# template_esp32.net
KiCad netlist of a schematic drawn in EAGLE
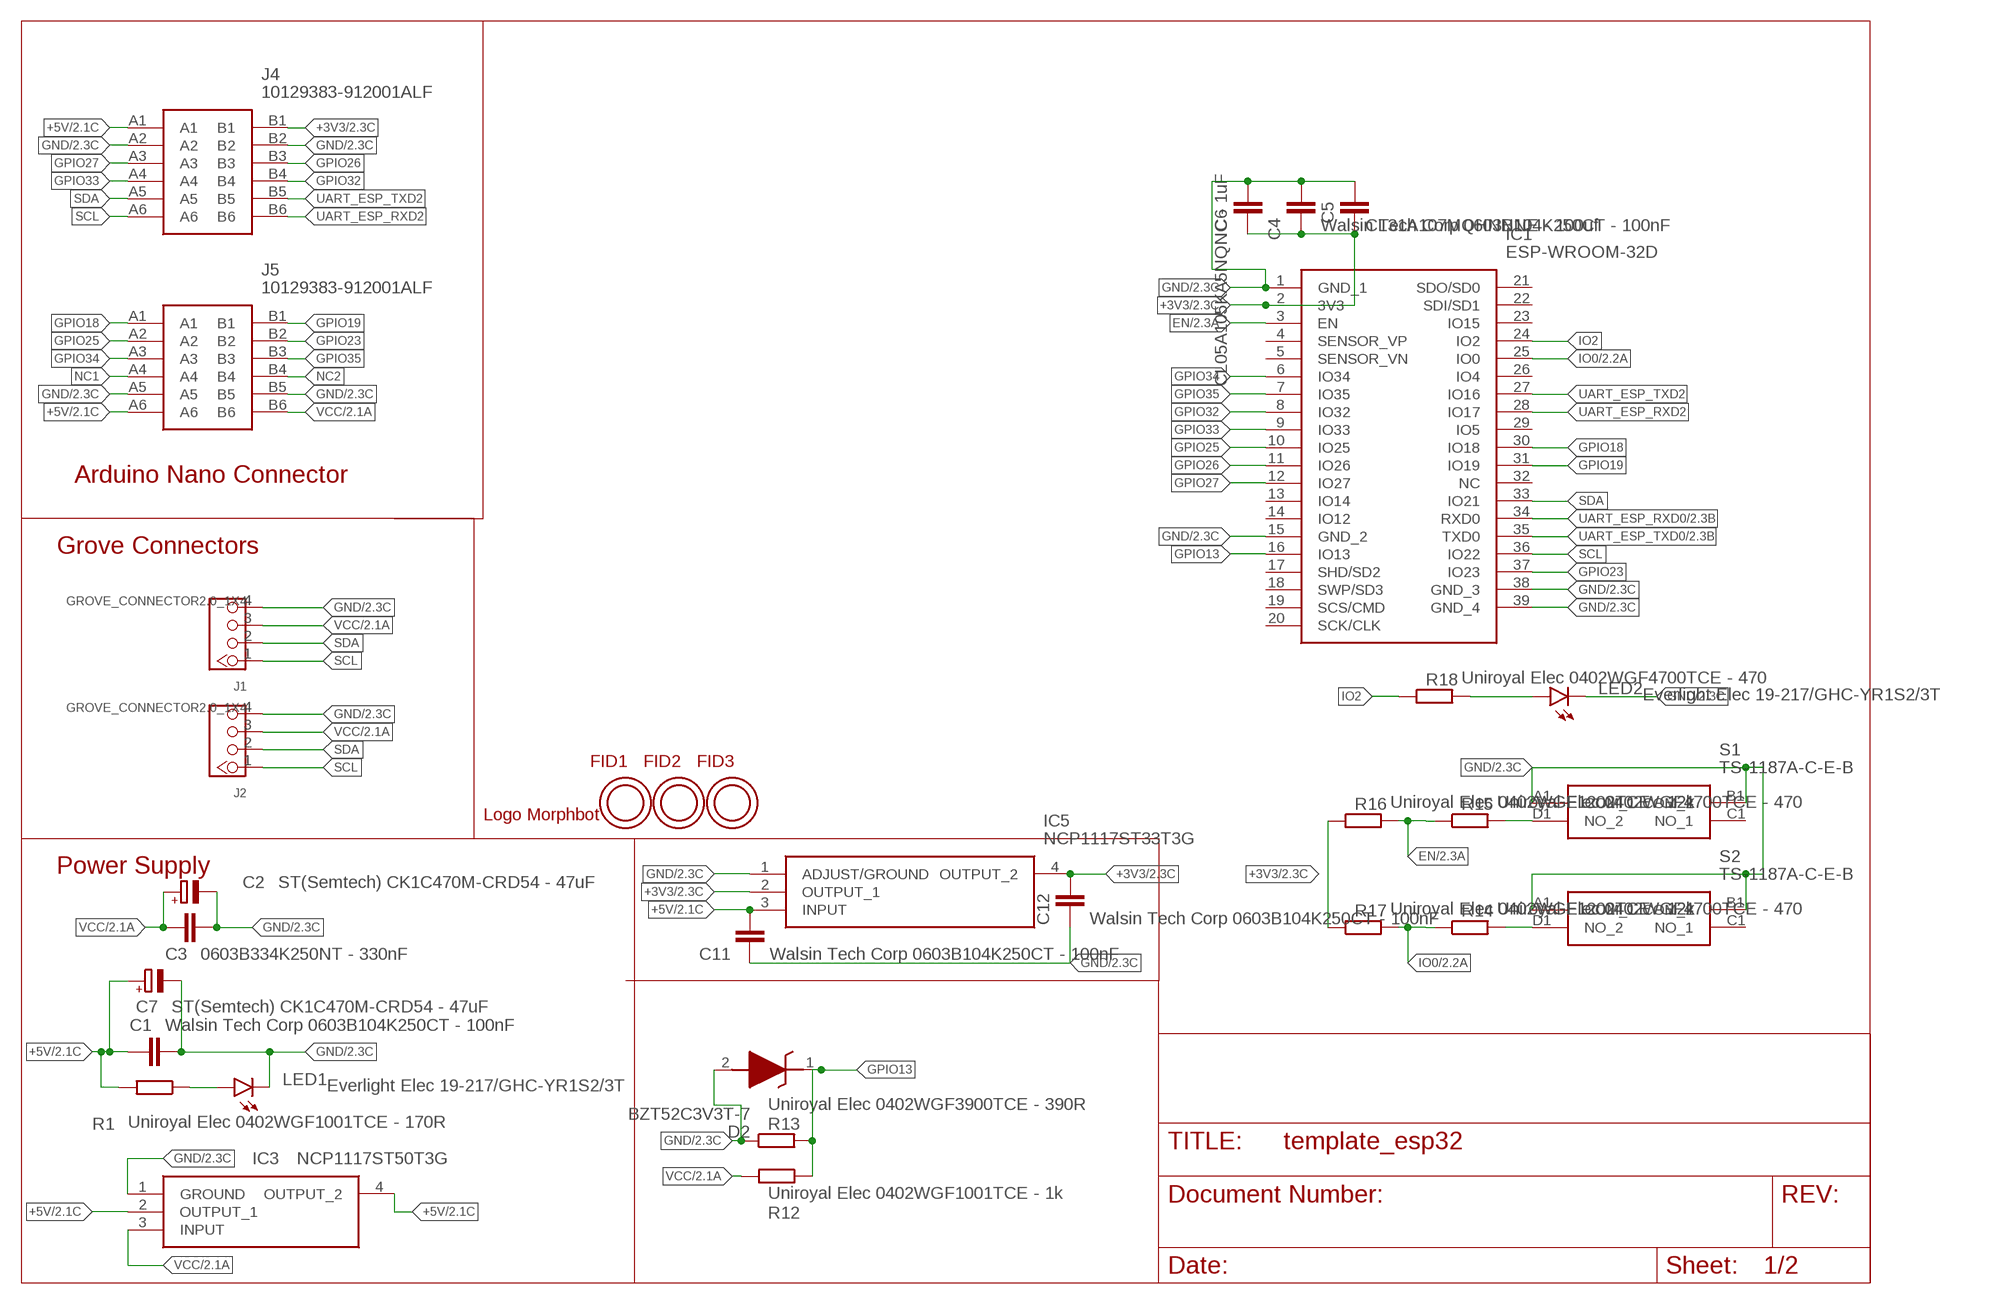
[diagram p0: schematic, sheet 1]
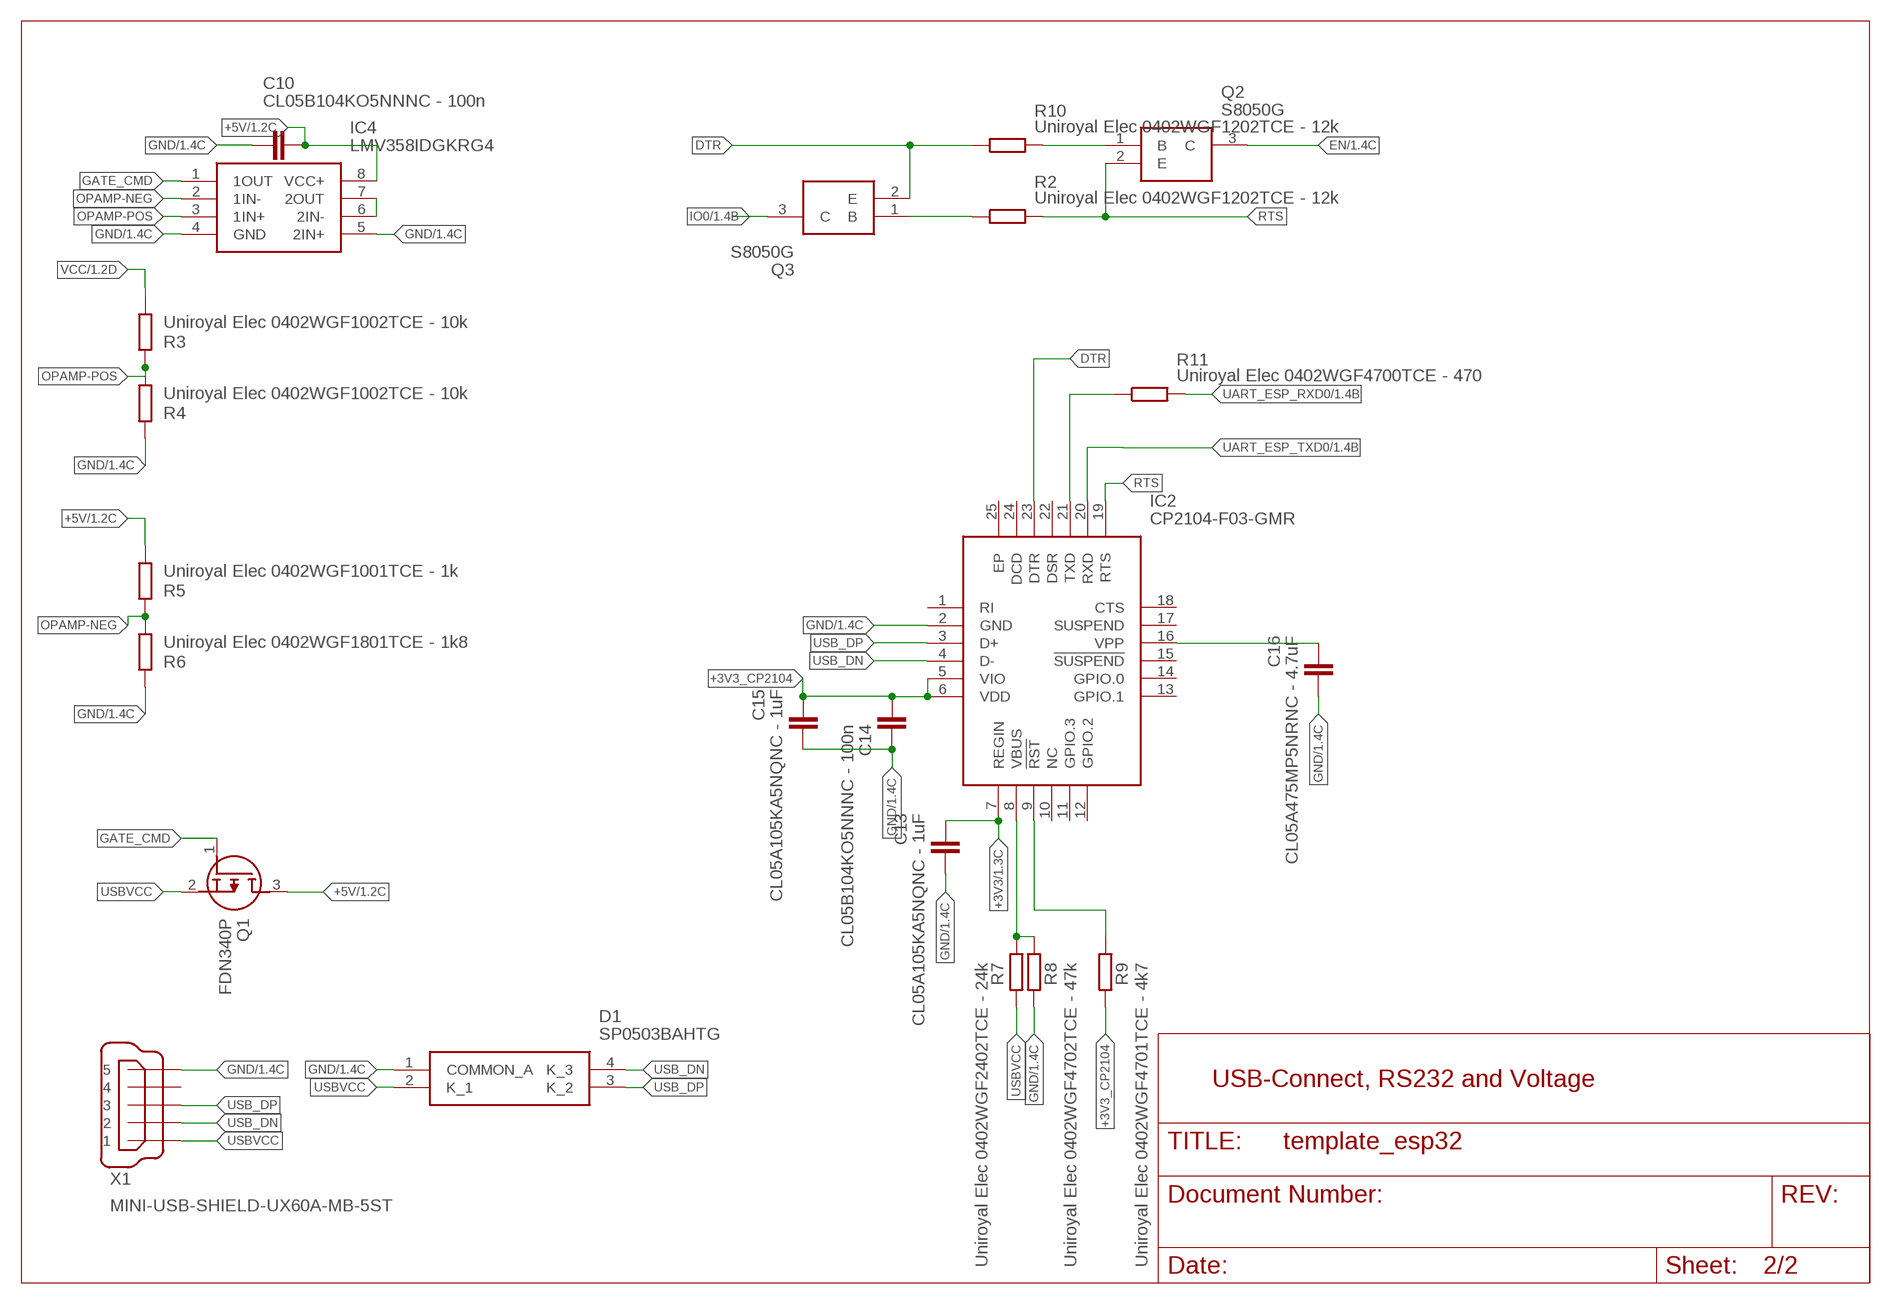
[diagram p1: schematic, sheet 2]

(export (version "E")
  (design (tool "Eeschema 10.0.6"))
  (components
    (comp (ref "C1")
      (value "Walsin Tech Corp 0603B104K250CT - 100nF")
      (footprint "eagle-import:C0603")
      (libsource (lib "eagle-import") (part "C-EUC0603"))
    )
    (comp (ref "C2")
      (value "ST(Semtech) CK1C470M-CRD54 - 47uF")
      (footprint "eagle-import:PANASONIC_C")
      (libsource (lib "eagle-import") (part "CPOL-EUC"))
    )
    (comp (ref "C3")
      (value "0603B334K250NT - 330nF")
      (footprint "eagle-import:C0603")
      (libsource (lib "eagle-import") (part "C-EUC0603"))
    )
    (comp (ref "C4")
      (value "Walsin Tech Corp 0603B104K250CT - 100nF")
      (footprint "eagle-import:C0603")
      (libsource (lib "eagle-import") (part "C-EUC0603"))
    )
    (comp (ref "C5")
      (value "CL31A107MQHNNNE - 100uf")
      (footprint "eagle-import:C1206")
      (libsource (lib "eagle-import") (part "C-EUC1206"))
    )
    (comp (ref "C6")
      (value "CL05A105KA5NQNC - 1uF")
      (footprint "eagle-import:C0402")
      (libsource (lib "eagle-import") (part "C-EUC0402"))
    )
    (comp (ref "C7")
      (value "ST(Semtech) CK1C470M-CRD54 - 47uF")
      (footprint "eagle-import:PANASONIC_C")
      (libsource (lib "eagle-import") (part "CPOL-EUC"))
    )
    (comp (ref "C11")
      (value "Walsin Tech Corp 0603B104K250CT - 100nF")
      (footprint "eagle-import:C0603")
      (libsource (lib "eagle-import") (part "C-EUC0603"))
    )
    (comp (ref "C12")
      (value "Walsin Tech Corp 0603B104K250CT - 100nF")
      (footprint "eagle-import:C0603")
      (libsource (lib "eagle-import") (part "C-EUC0603"))
    )
    (comp (ref "D2")
      (value "BZT52C3V3T-7")
      (footprint "eagle-import:SODFL1608X65N")
      (fields (field (name "MOUSER_PART_NUMBER") "621-BZT52C3V3T-7"))
      (libsource (lib "eagle-import") (part "BZT52C3V3T-7"))
    )
    (comp (ref "FID1")
      (value "OPEN-PNP-FIDUCIAL")
      (footprint "eagle-import:OPEN-PNP-FIDUCIAL")
      (libsource (lib "eagle-import") (part "OPEN-PNP-FIDUCIAL"))
    )
    (comp (ref "FID2")
      (value "OPEN-PNP-FIDUCIAL")
      (footprint "eagle-import:OPEN-PNP-FIDUCIAL")
      (libsource (lib "eagle-import") (part "OPEN-PNP-FIDUCIAL"))
    )
    (comp (ref "FID3")
      (value "OPEN-PNP-FIDUCIAL")
      (footprint "eagle-import:OPEN-PNP-FIDUCIAL")
      (libsource (lib "eagle-import") (part "OPEN-PNP-FIDUCIAL"))
    )
    (comp (ref "IC1")
      (value "ESP-WROOM-32D")
      (footprint "eagle-import:ESPWROOM32D")
      (fields (field (name "MOUSER_PART_NUMBER") "356-ESP-WROOM-32D"))
      (libsource (lib "eagle-import") (part "ESP-WROOM-32D"))
    )
    (comp (ref "IC3")
      (value "NCP1117ST50T3G")
      (footprint "eagle-import:SOT230P700X180-4N")
      (fields (field (name "MOUSER_PART_NUMBER") "863-NCP1117ST50T3G"))
      (libsource (lib "eagle-import") (part "NCP1117ST50T3G"))
    )
    (comp (ref "IC5")
      (value "NCP1117ST33T3G")
      (footprint "eagle-import:SOT230P700X180-4N")
      (fields (field (name "MOUSER_PART_NUMBER") "863-NCP1117ST33T3G"))
      (libsource (lib "eagle-import") (part "NCP1117ST33T3G"))
    )
    (comp (ref "J1")
      (value "GROVE_CONNECTOR2.0_1X4")
      (footprint "eagle-import:2.0_1X4_STRAIGHT")
      (libsource (lib "eagle-import") (part "GROVE_CONNECTOR2.0_1X4"))
    )
    (comp (ref "J2")
      (value "GROVE_CONNECTOR2.0_1X4")
      (footprint "eagle-import:2.0_1X4_STRAIGHT")
      (libsource (lib "eagle-import") (part "GROVE_CONNECTOR2.0_1X4"))
    )
    (comp (ref "J4")
      (value "10129383-912001ALF")
      (footprint "eagle-import:10129383912001ALF")
      (fields (field (name "MOUSER_PART_NUMBER") "649-1012938391201ALF"))
      (libsource (lib "eagle-import") (part "10129383-912001ALF"))
    )
    (comp (ref "J5")
      (value "10129383-912001ALF")
      (footprint "eagle-import:10129383912001ALF")
      (fields (field (name "MOUSER_PART_NUMBER") "649-1012938391201ALF"))
      (libsource (lib "eagle-import") (part "10129383-912001ALF"))
    )
    (comp (ref "LED1")
      (value "Everlight Elec 19-217/GHC-YR1S2/3T")
      (footprint "eagle-import:CHIPLED_0603")
      (libsource (lib "eagle-import") (part "LEDCHIPLED_0603"))
    )
    (comp (ref "LED2")
      (value "Everlight Elec 19-217/GHC-YR1S2/3T")
      (footprint "eagle-import:CHIPLED_0603")
      (libsource (lib "eagle-import") (part "LEDCHIPLED_0603"))
    )
    (comp (ref "R1")
      (value "Uniroyal Elec 0402WGF1001TCE - 170R")
      (footprint "eagle-import:R0402")
      (libsource (lib "eagle-import") (part "R-EU_R0402"))
    )
    (comp (ref "R12")
      (value "Uniroyal Elec 0402WGF1001TCE - 1k")
      (footprint "eagle-import:R0402")
      (libsource (lib "eagle-import") (part "R-EU_R0402"))
    )
    (comp (ref "R13")
      (value "Uniroyal Elec 0402WGF3900TCE - 390R")
      (footprint "eagle-import:R0402")
      (libsource (lib "eagle-import") (part "R-EU_R0402"))
    )
    (comp (ref "R14")
      (value "Uniroyal Elec 0402WGF4700TCE - 470")
      (footprint "eagle-import:R0402")
      (libsource (lib "eagle-import") (part "R-EU_R0402"))
    )
    (comp (ref "R15")
      (value "Uniroyal Elec 0402WGF4700TCE - 470")
      (footprint "eagle-import:R0402")
      (libsource (lib "eagle-import") (part "R-EU_R0402"))
    )
    (comp (ref "R16")
      (value "Uniroyal Elec 0402WGF1202TCE - 12k")
      (footprint "eagle-import:R0402")
      (libsource (lib "eagle-import") (part "R-EU_R0402"))
    )
    (comp (ref "R17")
      (value "Uniroyal Elec 0402WGF1202TCE - 12k")
      (footprint "eagle-import:R0402")
      (libsource (lib "eagle-import") (part "R-EU_R0402"))
    )
    (comp (ref "R18")
      (value "Uniroyal Elec 0402WGF4700TCE - 470")
      (footprint "eagle-import:R0402")
      (libsource (lib "eagle-import") (part "R-EU_R0402"))
    )
    (comp (ref "S1")
      (value "TS-1187A-C-E-B")
      (footprint "eagle-import:TS1187ACEB")
      (libsource (lib "eagle-import") (part "TS-1187A-C-E-B"))
    )
    (comp (ref "S2")
      (value "TS-1187A-C-E-B")
      (footprint "eagle-import:TS1187ACEB")
      (libsource (lib "eagle-import") (part "TS-1187A-C-E-B"))
    )
    (comp (ref "U$1")
      (value "LOGO_MORPHBOT3MM")
      (footprint "eagle-import:LOGO_MOPRHBOT_3MM")
      (libsource (lib "eagle-import") (part "LOGO_MORPHBOT3MM"))
    )
    (comp (ref "C10")
      (value "CL05B104KO5NNNC - 100n")
      (footprint "eagle-import:C0402")
      (libsource (lib "eagle-import") (part "C-EUC0402"))
    )
    (comp (ref "C13")
      (value "CL05A105KA5NQNC - 1uF")
      (footprint "eagle-import:C0402")
      (libsource (lib "eagle-import") (part "C-EUC0402"))
    )
    (comp (ref "C14")
      (value "CL05B104KO5NNNC - 100n")
      (footprint "eagle-import:C0402")
      (libsource (lib "eagle-import") (part "C-EUC0402"))
    )
    (comp (ref "C15")
      (value "CL05A105KA5NQNC - 1uF")
      (footprint "eagle-import:C0402")
      (libsource (lib "eagle-import") (part "C-EUC0402"))
    )
    (comp (ref "C16")
      (value "CL05A475MP5NRNC - 4.7uF")
      (footprint "eagle-import:C0402")
      (libsource (lib "eagle-import") (part "C-EUC0402"))
    )
    (comp (ref "D1")
      (value "SP0503BAHTG")
      (footprint "eagle-import:SP0503BAHTG")
      (fields (field (name "MOUSER_PART_NUMBER") "576-SP0503BAHTG"))
      (libsource (lib "eagle-import") (part "SP0503BAHTG"))
    )
    (comp (ref "IC2")
      (value "CP2104-F03-GMR")
      (footprint "eagle-import:QFN50P400X400X80-25N")
      (fields (field (name "MOUSER_PART_NUMBER") "634-CP2104-F03-GMR"))
      (libsource (lib "eagle-import") (part "CP2104-F03-GMR"))
    )
    (comp (ref "IC4")
      (value "LMV358IDGKRG4")
      (footprint "eagle-import:SOP65P490X110-8N")
      (fields (field (name "MOUSER_PART_NUMBER") "595-LMV358IDGKRG4"))
      (libsource (lib "eagle-import") (part "LMV358IDGKRG4"))
    )
    (comp (ref "Q1")
      (value "FDN340P")
      (footprint "eagle-import:SOT95P237X112-3N")
      (fields (field (name "MOUSER_PART_NUMBER") "512-FDN340P"))
      (libsource (lib "eagle-import") (part "FDN340P"))
    )
    (comp (ref "Q2")
      (value "S8050G")
      (footprint "eagle-import:SOT95P240X110-3N")
      (libsource (lib "eagle-import") (part "S8050G"))
    )
    (comp (ref "Q3")
      (value "S8050G")
      (footprint "eagle-import:SOT95P240X110-3N")
      (libsource (lib "eagle-import") (part "S8050G"))
    )
    (comp (ref "R2")
      (value "Uniroyal Elec 0402WGF1202TCE - 12k")
      (footprint "eagle-import:R0402")
      (libsource (lib "eagle-import") (part "R-EU_R0402"))
    )
    (comp (ref "R3")
      (value "Uniroyal Elec 0402WGF1002TCE - 10k")
      (footprint "eagle-import:R0402")
      (libsource (lib "eagle-import") (part "R-EU_R0402"))
    )
    (comp (ref "R4")
      (value "Uniroyal Elec 0402WGF1002TCE - 10k")
      (footprint "eagle-import:R0402")
      (libsource (lib "eagle-import") (part "R-EU_R0402"))
    )
    (comp (ref "R5")
      (value "Uniroyal Elec 0402WGF1001TCE - 1k")
      (footprint "eagle-import:R0402")
      (libsource (lib "eagle-import") (part "R-EU_R0402"))
    )
    (comp (ref "R6")
      (value "Uniroyal Elec 0402WGF1801TCE - 1k8")
      (footprint "eagle-import:R0402")
      (libsource (lib "eagle-import") (part "R-EU_R0402"))
    )
    (comp (ref "R7")
      (value "Uniroyal Elec 0402WGF2402TCE - 24k")
      (footprint "eagle-import:R0402")
      (libsource (lib "eagle-import") (part "R-EU_R0402"))
    )
    (comp (ref "R8")
      (value "Uniroyal Elec 0402WGF4702TCE - 47k")
      (footprint "eagle-import:R0402")
      (libsource (lib "eagle-import") (part "R-EU_R0402"))
    )
    (comp (ref "R9")
      (value "Uniroyal Elec 0402WGF4701TCE - 4k7")
      (footprint "eagle-import:R0402")
      (libsource (lib "eagle-import") (part "R-EU_R0402"))
    )
    (comp (ref "R10")
      (value "Uniroyal Elec 0402WGF1202TCE - 12k")
      (footprint "eagle-import:R0402")
      (libsource (lib "eagle-import") (part "R-EU_R0402"))
    )
    (comp (ref "R11")
      (value "Uniroyal Elec 0402WGF4700TCE - 470")
      (footprint "eagle-import:R0402")
      (libsource (lib "eagle-import") (part "R-EU_R0402"))
    )
    (comp (ref "X1")
      (value "MINI-USB-SHIELD-UX60A-MB-5ST")
      (footprint "eagle-import:UX60A-MB-5ST")
      (libsource (lib "eagle-import") (part "MINI-USB-SHIELD-UX60A-MB-5ST"))
    )
  )
  (nets
    (net (code "1") (name "+3V3") (class "Default")
      (node (ref "C12") (pin "2") (pinfunction "2_2") (pintype "passive"))
      (node (ref "C13") (pin "2") (pinfunction "2_2") (pintype "passive"))
      (node (ref "C4") (pin "1") (pinfunction "1_1") (pintype "passive"))
      (node (ref "C5") (pin "2") (pinfunction "2_2") (pintype "passive"))
      (node (ref "C6") (pin "1") (pinfunction "1_1") (pintype "passive"))
      (node (ref "IC1") (pin "2") (pinfunction "3V3_2") (pintype "bidirectional"))
      (node (ref "IC2") (pin "7") (pinfunction "REGIN_7") (pintype "bidirectional"))
      (node (ref "IC5") (pin "2") (pinfunction "OUTPUT_1_2") (pintype "bidirectional"))
      (node (ref "IC5") (pin "4") (pinfunction "OUTPUT_2_4") (pintype "bidirectional"))
      (node (ref "J4") (pin "B1") (pinfunction "B1_B1") (pintype "bidirectional"))
      (node (ref "R16") (pin "1") (pinfunction "1_1") (pintype "passive"))
      (node (ref "R17") (pin "1") (pinfunction "1_1") (pintype "passive"))
    )
    (net (code "2") (name "+3V3_CP2104") (class "Default")
      (node (ref "C14") (pin "2") (pinfunction "2_2") (pintype "passive"))
      (node (ref "C15") (pin "2") (pinfunction "2_2") (pintype "passive"))
      (node (ref "IC2") (pin "5") (pinfunction "VIO_5") (pintype "bidirectional"))
      (node (ref "IC2") (pin "6") (pinfunction "VDD_6") (pintype "bidirectional"))
      (node (ref "R9") (pin "2") (pinfunction "2_2") (pintype "passive"))
    )
    (net (code "3") (name "+5V") (class "Default")
      (node (ref "C1") (pin "1") (pinfunction "1_1") (pintype "passive"))
      (node (ref "C10") (pin "2") (pinfunction "2_2") (pintype "passive"))
      (node (ref "C11") (pin "2") (pinfunction "2_2") (pintype "passive"))
      (node (ref "C7") (pin "+") (pinfunction "+_+") (pintype "passive"))
      (node (ref "IC3") (pin "2") (pinfunction "OUTPUT_1_2") (pintype "bidirectional"))
      (node (ref "IC3") (pin "4") (pinfunction "OUTPUT_2_4") (pintype "bidirectional"))
      (node (ref "IC4") (pin "8") (pinfunction "VCC+_8") (pintype "bidirectional"))
      (node (ref "IC5") (pin "3") (pinfunction "INPUT_3") (pintype "bidirectional"))
      (node (ref "J4") (pin "A1") (pinfunction "A1_A1") (pintype "bidirectional"))
      (node (ref "J5") (pin "A6") (pinfunction "A6_A6") (pintype "bidirectional"))
      (node (ref "Q1") (pin "3") (pinfunction "D_3") (pintype "bidirectional"))
      (node (ref "R1") (pin "2") (pinfunction "2_2") (pintype "passive"))
      (node (ref "R5") (pin "1") (pinfunction "1_1") (pintype "passive"))
    )
    (net (code "4") (name "DTR") (class "Default")
      (node (ref "IC2") (pin "23") (pinfunction "DTR_23") (pintype "bidirectional"))
      (node (ref "Q3") (pin "2") (pinfunction "E_2") (pintype "bidirectional"))
      (node (ref "R10") (pin "1") (pinfunction "1_1") (pintype "passive"))
    )
    (net (code "5") (name "EN") (class "Default")
      (node (ref "IC1") (pin "3") (pinfunction "EN_3") (pintype "bidirectional"))
      (node (ref "Q2") (pin "3") (pinfunction "C_3") (pintype "bidirectional"))
      (node (ref "R15") (pin "1") (pinfunction "1_1") (pintype "passive"))
      (node (ref "R16") (pin "2") (pinfunction "2_2") (pintype "passive"))
    )
    (net (code "6") (name "GATE_CMD") (class "Default")
      (node (ref "IC4") (pin "1") (pinfunction "1OUT_1") (pintype "bidirectional"))
      (node (ref "Q1") (pin "1") (pinfunction "G_1") (pintype "bidirectional"))
    )
    (net (code "7") (name "GND") (class "Default")
      (node (ref "C1") (pin "2") (pinfunction "2_2") (pintype "passive"))
      (node (ref "C10") (pin "1") (pinfunction "1_1") (pintype "passive"))
      (node (ref "C11") (pin "1") (pinfunction "1_1") (pintype "passive"))
      (node (ref "C12") (pin "1") (pinfunction "1_1") (pintype "passive"))
      (node (ref "C13") (pin "1") (pinfunction "1_1") (pintype "passive"))
      (node (ref "C14") (pin "1") (pinfunction "1_1") (pintype "passive"))
      (node (ref "C15") (pin "1") (pinfunction "1_1") (pintype "passive"))
      (node (ref "C16") (pin "1") (pinfunction "1_1") (pintype "passive"))
      (node (ref "C2") (pin "-") (pinfunction "-_-") (pintype "passive"))
      (node (ref "C3") (pin "1") (pinfunction "1_1") (pintype "passive"))
      (node (ref "C4") (pin "2") (pinfunction "2_2") (pintype "passive"))
      (node (ref "C5") (pin "1") (pinfunction "1_1") (pintype "passive"))
      (node (ref "C6") (pin "2") (pinfunction "2_2") (pintype "passive"))
      (node (ref "C7") (pin "-") (pinfunction "-_-") (pintype "passive"))
      (node (ref "D1") (pin "1") (pinfunction "COMMON_A_1") (pintype "bidirectional"))
      (node (ref "D2") (pin "2") (pinfunction "A_2") (pintype "bidirectional"))
      (node (ref "IC1") (pin "1") (pinfunction "GND_1_1") (pintype "bidirectional"))
      (node (ref "IC1") (pin "15") (pinfunction "GND_2_15") (pintype "bidirectional"))
      (node (ref "IC1") (pin "38") (pinfunction "GND_3_38") (pintype "bidirectional"))
      (node (ref "IC1") (pin "39") (pinfunction "GND_4_39") (pintype "bidirectional"))
      (node (ref "IC2") (pin "2") (pinfunction "GND_2") (pintype "bidirectional"))
      (node (ref "IC3") (pin "1") (pinfunction "GROUND_1") (pintype "bidirectional"))
      (node (ref "IC4") (pin "4") (pinfunction "GND_4") (pintype "bidirectional"))
      (node (ref "IC4") (pin "5") (pinfunction "2IN+_5") (pintype "bidirectional"))
      (node (ref "IC5") (pin "1") (pinfunction "ADJUST/GROUND_1") (pintype "bidirectional"))
      (node (ref "J1") (pin "4") (pinfunction "4_4") (pintype "bidirectional"))
      (node (ref "J2") (pin "4") (pinfunction "4_4") (pintype "bidirectional"))
      (node (ref "J4") (pin "A2") (pinfunction "A2_A2") (pintype "bidirectional"))
      (node (ref "J4") (pin "B2") (pinfunction "B2_B2") (pintype "bidirectional"))
      (node (ref "J5") (pin "A5") (pinfunction "A5_A5") (pintype "bidirectional"))
      (node (ref "J5") (pin "B5") (pinfunction "B5_B5") (pintype "bidirectional"))
      (node (ref "LED1") (pin "C") (pinfunction "C_C") (pintype "passive"))
      (node (ref "LED2") (pin "C") (pinfunction "C_C") (pintype "passive"))
      (node (ref "R13") (pin "1") (pinfunction "1_1") (pintype "passive"))
      (node (ref "R4") (pin "2") (pinfunction "2_2") (pintype "passive"))
      (node (ref "R6") (pin "2") (pinfunction "2_2") (pintype "passive"))
      (node (ref "R8") (pin "2") (pinfunction "2_2") (pintype "passive"))
      (node (ref "S1") (pin "A1") (pinfunction "COM_1_A1") (pintype "bidirectional"))
      (node (ref "S1") (pin "B1") (pinfunction "COM_2_B1") (pintype "bidirectional"))
      (node (ref "S2") (pin "A1") (pinfunction "COM_1_A1") (pintype "bidirectional"))
      (node (ref "S2") (pin "B1") (pinfunction "COM_2_B1") (pintype "bidirectional"))
      (node (ref "X1") (pin "5") (pinfunction "5_5") (pintype "input"))
    )
    (net (code "8") (name "GPIO13") (class "Default")
      (node (ref "D2") (pin "1") (pinfunction "K_1") (pintype "bidirectional"))
      (node (ref "IC1") (pin "16") (pinfunction "IO13_16") (pintype "bidirectional"))
      (node (ref "R12") (pin "1") (pinfunction "1_1") (pintype "passive"))
      (node (ref "R13") (pin "2") (pinfunction "2_2") (pintype "passive"))
    )
    (net (code "9") (name "GPIO18") (class "Default")
      (node (ref "IC1") (pin "30") (pinfunction "IO18_30") (pintype "bidirectional"))
      (node (ref "J5") (pin "A1") (pinfunction "A1_A1") (pintype "bidirectional"))
    )
    (net (code "10") (name "GPIO19") (class "Default")
      (node (ref "IC1") (pin "31") (pinfunction "IO19_31") (pintype "bidirectional"))
      (node (ref "J5") (pin "B1") (pinfunction "B1_B1") (pintype "bidirectional"))
    )
    (net (code "11") (name "GPIO23") (class "Default")
      (node (ref "IC1") (pin "37") (pinfunction "IO23_37") (pintype "bidirectional"))
      (node (ref "J5") (pin "B2") (pinfunction "B2_B2") (pintype "bidirectional"))
    )
    (net (code "12") (name "GPIO25") (class "Default")
      (node (ref "IC1") (pin "10") (pinfunction "IO25_10") (pintype "bidirectional"))
      (node (ref "J5") (pin "A2") (pinfunction "A2_A2") (pintype "bidirectional"))
    )
    (net (code "13") (name "GPIO26") (class "Default")
      (node (ref "IC1") (pin "11") (pinfunction "IO26_11") (pintype "bidirectional"))
      (node (ref "J4") (pin "B3") (pinfunction "B3_B3") (pintype "bidirectional"))
    )
    (net (code "14") (name "GPIO27") (class "Default")
      (node (ref "IC1") (pin "12") (pinfunction "IO27_12") (pintype "bidirectional"))
      (node (ref "J4") (pin "A3") (pinfunction "A3_A3") (pintype "bidirectional"))
    )
    (net (code "15") (name "GPIO32") (class "Default")
      (node (ref "IC1") (pin "8") (pinfunction "IO32_8") (pintype "bidirectional"))
      (node (ref "J4") (pin "B4") (pinfunction "B4_B4") (pintype "bidirectional"))
    )
    (net (code "16") (name "GPIO33") (class "Default")
      (node (ref "IC1") (pin "9") (pinfunction "IO33_9") (pintype "bidirectional"))
      (node (ref "J4") (pin "A4") (pinfunction "A4_A4") (pintype "bidirectional"))
    )
    (net (code "17") (name "GPIO34") (class "Default")
      (node (ref "IC1") (pin "6") (pinfunction "IO34_6") (pintype "bidirectional"))
      (node (ref "J5") (pin "A3") (pinfunction "A3_A3") (pintype "bidirectional"))
    )
    (net (code "18") (name "GPIO35") (class "Default")
      (node (ref "IC1") (pin "7") (pinfunction "IO35_7") (pintype "bidirectional"))
      (node (ref "J5") (pin "B3") (pinfunction "B3_B3") (pintype "bidirectional"))
    )
    (net (code "19") (name "IO0") (class "Default")
      (node (ref "IC1") (pin "25") (pinfunction "IO0_25") (pintype "bidirectional"))
      (node (ref "Q3") (pin "3") (pinfunction "C_3") (pintype "bidirectional"))
      (node (ref "R14") (pin "1") (pinfunction "1_1") (pintype "passive"))
      (node (ref "R17") (pin "2") (pinfunction "2_2") (pintype "passive"))
    )
    (net (code "20") (name "IO2") (class "Default")
      (node (ref "IC1") (pin "24") (pinfunction "IO2_24") (pintype "bidirectional"))
      (node (ref "R18") (pin "1") (pinfunction "1_1") (pintype "passive"))
    )
    (net (code "21") (name "NC1") (class "Default")
      (node (ref "J5") (pin "A4") (pinfunction "A4_A4") (pintype "bidirectional"))
    )
    (net (code "22") (name "NC2") (class "Default")
      (node (ref "J5") (pin "B4") (pinfunction "B4_B4") (pintype "bidirectional"))
    )
    (net (code "23") (name "Net-(IC2-TXD)") (class "Default")
      (node (ref "IC2") (pin "21") (pinfunction "TXD_21") (pintype "bidirectional"))
      (node (ref "R11") (pin "1") (pinfunction "1_1") (pintype "passive"))
    )
    (net (code "24") (name "Net-(IC2-VBUS)") (class "Default")
      (node (ref "IC2") (pin "8") (pinfunction "VBUS_8") (pintype "bidirectional"))
      (node (ref "R7") (pin "1") (pinfunction "1_1") (pintype "passive"))
      (node (ref "R8") (pin "1") (pinfunction "1_1") (pintype "passive"))
    )
    (net (code "25") (name "Net-(IC2-VPP)") (class "Default")
      (node (ref "C16") (pin "2") (pinfunction "2_2") (pintype "passive"))
      (node (ref "IC2") (pin "16") (pinfunction "VPP_16") (pintype "bidirectional"))
    )
    (net (code "26") (name "Net-(IC2-~{RST})") (class "Default")
      (node (ref "IC2") (pin "9") (pinfunction "~{RST}_9") (pintype "bidirectional"))
      (node (ref "R9") (pin "1") (pinfunction "1_1") (pintype "passive"))
    )
    (net (code "27") (name "Net-(IC4-2IN-)") (class "Default")
      (node (ref "IC4") (pin "6") (pinfunction "2IN-_6") (pintype "bidirectional"))
      (node (ref "IC4") (pin "7") (pinfunction "2OUT_7") (pintype "bidirectional"))
    )
    (net (code "28") (name "Net-(LED1-PadA)") (class "Default")
      (node (ref "LED1") (pin "A") (pinfunction "A_A") (pintype "passive"))
      (node (ref "R1") (pin "1") (pinfunction "1_1") (pintype "passive"))
    )
    (net (code "29") (name "Net-(LED2-PadA)") (class "Default")
      (node (ref "LED2") (pin "A") (pinfunction "A_A") (pintype "passive"))
      (node (ref "R18") (pin "2") (pinfunction "2_2") (pintype "passive"))
    )
    (net (code "30") (name "Net-(Q2-B)") (class "Default")
      (node (ref "Q2") (pin "1") (pinfunction "B_1") (pintype "bidirectional"))
      (node (ref "R10") (pin "2") (pinfunction "2_2") (pintype "passive"))
    )
    (net (code "31") (name "Net-(Q3-B)") (class "Default")
      (node (ref "Q3") (pin "1") (pinfunction "B_1") (pintype "bidirectional"))
      (node (ref "R2") (pin "1") (pinfunction "1_1") (pintype "passive"))
    )
    (net (code "32") (name "Net-(S1-NO_2)") (class "Default")
      (node (ref "R15") (pin "2") (pinfunction "2_2") (pintype "passive"))
      (node (ref "S1") (pin "D1") (pinfunction "NO_2_D1") (pintype "bidirectional"))
    )
    (net (code "33") (name "Net-(S2-NO_2)") (class "Default")
      (node (ref "R14") (pin "2") (pinfunction "2_2") (pintype "passive"))
      (node (ref "S2") (pin "D1") (pinfunction "NO_2_D1") (pintype "bidirectional"))
    )
    (net (code "34") (name "OPAMP-NEG") (class "Default")
      (node (ref "IC4") (pin "2") (pinfunction "1IN-_2") (pintype "bidirectional"))
      (node (ref "R5") (pin "2") (pinfunction "2_2") (pintype "passive"))
      (node (ref "R6") (pin "1") (pinfunction "1_1") (pintype "passive"))
    )
    (net (code "35") (name "OPAMP-POS") (class "Default")
      (node (ref "IC4") (pin "3") (pinfunction "1IN+_3") (pintype "bidirectional"))
      (node (ref "R3") (pin "2") (pinfunction "2_2") (pintype "passive"))
      (node (ref "R4") (pin "1") (pinfunction "1_1") (pintype "passive"))
    )
    (net (code "36") (name "RTS") (class "Default")
      (node (ref "IC2") (pin "19") (pinfunction "RTS_19") (pintype "bidirectional"))
      (node (ref "Q2") (pin "2") (pinfunction "E_2") (pintype "bidirectional"))
      (node (ref "R2") (pin "2") (pinfunction "2_2") (pintype "passive"))
    )
    (net (code "37") (name "SCL") (class "Default")
      (node (ref "IC1") (pin "36") (pinfunction "IO22_36") (pintype "bidirectional"))
      (node (ref "J1") (pin "1") (pinfunction "1_1") (pintype "bidirectional"))
      (node (ref "J2") (pin "1") (pinfunction "1_1") (pintype "bidirectional"))
      (node (ref "J4") (pin "A6") (pinfunction "A6_A6") (pintype "bidirectional"))
    )
    (net (code "38") (name "SDA") (class "Default")
      (node (ref "IC1") (pin "33") (pinfunction "IO21_33") (pintype "bidirectional"))
      (node (ref "J1") (pin "2") (pinfunction "2_2") (pintype "bidirectional"))
      (node (ref "J2") (pin "2") (pinfunction "2_2") (pintype "bidirectional"))
      (node (ref "J4") (pin "A5") (pinfunction "A5_A5") (pintype "bidirectional"))
    )
    (net (code "39") (name "UART_ESP_RXD0") (class "Default")
      (node (ref "IC1") (pin "34") (pinfunction "RXD0_34") (pintype "bidirectional"))
      (node (ref "R11") (pin "2") (pinfunction "2_2") (pintype "passive"))
    )
    (net (code "40") (name "UART_ESP_RXD2") (class "Default")
      (node (ref "IC1") (pin "28") (pinfunction "IO17_28") (pintype "bidirectional"))
      (node (ref "J4") (pin "B6") (pinfunction "B6_B6") (pintype "bidirectional"))
    )
    (net (code "41") (name "UART_ESP_TXD0") (class "Default")
      (node (ref "IC1") (pin "35") (pinfunction "TXD0_35") (pintype "bidirectional"))
      (node (ref "IC2") (pin "20") (pinfunction "RXD_20") (pintype "bidirectional"))
    )
    (net (code "42") (name "UART_ESP_TXD2") (class "Default")
      (node (ref "IC1") (pin "27") (pinfunction "IO16_27") (pintype "bidirectional"))
      (node (ref "J4") (pin "B5") (pinfunction "B5_B5") (pintype "bidirectional"))
    )
    (net (code "43") (name "USBVCC") (class "Default")
      (node (ref "D1") (pin "2") (pinfunction "K_1_2") (pintype "bidirectional"))
      (node (ref "Q1") (pin "2") (pinfunction "S_2") (pintype "bidirectional"))
      (node (ref "R7") (pin "2") (pinfunction "2_2") (pintype "passive"))
      (node (ref "X1") (pin "1") (pinfunction "1_1") (pintype "input"))
    )
    (net (code "44") (name "USB_DN") (class "Default")
      (node (ref "D1") (pin "4") (pinfunction "K_3_4") (pintype "bidirectional"))
      (node (ref "IC2") (pin "4") (pinfunction "D-_4") (pintype "bidirectional"))
      (node (ref "X1") (pin "2") (pinfunction "2_2") (pintype "input"))
    )
    (net (code "45") (name "USB_DP") (class "Default")
      (node (ref "D1") (pin "3") (pinfunction "K_2_3") (pintype "bidirectional"))
      (node (ref "IC2") (pin "3") (pinfunction "D+_3") (pintype "bidirectional"))
      (node (ref "X1") (pin "3") (pinfunction "3_3") (pintype "input"))
    )
    (net (code "46") (name "VCC") (class "Default")
      (node (ref "C2") (pin "+") (pinfunction "+_+") (pintype "passive"))
      (node (ref "C3") (pin "2") (pinfunction "2_2") (pintype "passive"))
      (node (ref "IC3") (pin "3") (pinfunction "INPUT_3") (pintype "bidirectional"))
      (node (ref "J1") (pin "3") (pinfunction "3_3") (pintype "bidirectional"))
      (node (ref "J2") (pin "3") (pinfunction "3_3") (pintype "bidirectional"))
      (node (ref "J5") (pin "B6") (pinfunction "B6_B6") (pintype "bidirectional"))
      (node (ref "R12") (pin "2") (pinfunction "2_2") (pintype "passive"))
      (node (ref "R3") (pin "1") (pinfunction "1_1") (pintype "passive"))
    )
    (net (code "47") (name "unconnected-(IC1-IO4-Pad26)") (class "Default")
      (node (ref "IC1") (pin "26") (pinfunction "IO4_26") (pintype "bidirectional"))
    )
    (net (code "48") (name "unconnected-(IC1-IO5-Pad29)") (class "Default")
      (node (ref "IC1") (pin "29") (pinfunction "IO5_29") (pintype "bidirectional"))
    )
    (net (code "49") (name "unconnected-(IC1-IO12-Pad14)") (class "Default")
      (node (ref "IC1") (pin "14") (pinfunction "IO12_14") (pintype "bidirectional"))
    )
    (net (code "50") (name "unconnected-(IC1-IO14-Pad13)") (class "Default")
      (node (ref "IC1") (pin "13") (pinfunction "IO14_13") (pintype "bidirectional"))
    )
    (net (code "51") (name "unconnected-(IC1-IO15-Pad23)") (class "Default")
      (node (ref "IC1") (pin "23") (pinfunction "IO15_23") (pintype "bidirectional"))
    )
    (net (code "52") (name "unconnected-(IC1-NC-Pad32)") (class "Default")
      (node (ref "IC1") (pin "32") (pinfunction "NC_32") (pintype "no_connect"))
    )
    (net (code "53") (name "unconnected-(IC1-SCK{slash}CLK-Pad20)") (class "Default")
      (node (ref "IC1") (pin "20") (pinfunction "SCK/CLK_20") (pintype "bidirectional"))
    )
    (net (code "54") (name "unconnected-(IC1-SCS{slash}CMD-Pad19)") (class "Default")
      (node (ref "IC1") (pin "19") (pinfunction "SCS/CMD_19") (pintype "bidirectional"))
    )
    (net (code "55") (name "unconnected-(IC1-SDI{slash}SD1-Pad22)") (class "Default")
      (node (ref "IC1") (pin "22") (pinfunction "SDI/SD1_22") (pintype "bidirectional"))
    )
    (net (code "56") (name "unconnected-(IC1-SDO{slash}SD0-Pad21)") (class "Default")
      (node (ref "IC1") (pin "21") (pinfunction "SDO/SD0_21") (pintype "bidirectional"))
    )
    (net (code "57") (name "unconnected-(IC1-SENSOR_VN-Pad5)") (class "Default")
      (node (ref "IC1") (pin "5") (pinfunction "SENSOR_VN_5") (pintype "bidirectional"))
    )
    (net (code "58") (name "unconnected-(IC1-SENSOR_VP-Pad4)") (class "Default")
      (node (ref "IC1") (pin "4") (pinfunction "SENSOR_VP_4") (pintype "bidirectional"))
    )
    (net (code "59") (name "unconnected-(IC1-SHD{slash}SD2-Pad17)") (class "Default")
      (node (ref "IC1") (pin "17") (pinfunction "SHD/SD2_17") (pintype "bidirectional"))
    )
    (net (code "60") (name "unconnected-(IC1-SWP{slash}SD3-Pad18)") (class "Default")
      (node (ref "IC1") (pin "18") (pinfunction "SWP/SD3_18") (pintype "bidirectional"))
    )
    (net (code "61") (name "unconnected-(IC2-CTS-Pad18)") (class "Default")
      (node (ref "IC2") (pin "18") (pinfunction "CTS_18") (pintype "bidirectional"))
    )
    (net (code "62") (name "unconnected-(IC2-DCD-Pad24)") (class "Default")
      (node (ref "IC2") (pin "24") (pinfunction "DCD_24") (pintype "bidirectional"))
    )
    (net (code "63") (name "unconnected-(IC2-DSR-Pad22)") (class "Default")
      (node (ref "IC2") (pin "22") (pinfunction "DSR_22") (pintype "bidirectional"))
    )
    (net (code "64") (name "unconnected-(IC2-EP-Pad25)") (class "Default")
      (node (ref "IC2") (pin "25") (pinfunction "EP_25") (pintype "bidirectional"))
    )
    (net (code "65") (name "unconnected-(IC2-GPIO.0-Pad14)") (class "Default")
      (node (ref "IC2") (pin "14") (pinfunction "GPIO.0_14") (pintype "bidirectional"))
    )
    (net (code "66") (name "unconnected-(IC2-GPIO.1-Pad13)") (class "Default")
      (node (ref "IC2") (pin "13") (pinfunction "GPIO.1_13") (pintype "bidirectional"))
    )
    (net (code "67") (name "unconnected-(IC2-GPIO.2-Pad12)") (class "Default")
      (node (ref "IC2") (pin "12") (pinfunction "GPIO.2_12") (pintype "bidirectional"))
    )
    (net (code "68") (name "unconnected-(IC2-GPIO.3-Pad11)") (class "Default")
      (node (ref "IC2") (pin "11") (pinfunction "GPIO.3_11") (pintype "bidirectional"))
    )
    (net (code "69") (name "unconnected-(IC2-NC-Pad10)") (class "Default")
      (node (ref "IC2") (pin "10") (pinfunction "NC_10") (pintype "no_connect"))
    )
    (net (code "70") (name "unconnected-(IC2-RI-Pad1)") (class "Default")
      (node (ref "IC2") (pin "1") (pinfunction "RI_1") (pintype "bidirectional"))
    )
    (net (code "71") (name "unconnected-(IC2-SUSPEND-Pad17)") (class "Default")
      (node (ref "IC2") (pin "17") (pinfunction "SUSPEND_17") (pintype "bidirectional"))
    )
    (net (code "72") (name "unconnected-(IC2-~{SUSPEND}-Pad15)") (class "Default")
      (node (ref "IC2") (pin "15") (pinfunction "~{SUSPEND}_15") (pintype "bidirectional"))
    )
    (net (code "73") (name "unconnected-(S1-NO_1-PadC1)") (class "Default")
      (node (ref "S1") (pin "C1") (pinfunction "NO_1_C1") (pintype "bidirectional"))
    )
    (net (code "74") (name "unconnected-(S2-NO_1-PadC1)") (class "Default")
      (node (ref "S2") (pin "C1") (pinfunction "NO_1_C1") (pintype "bidirectional"))
    )
    (net (code "75") (name "unconnected-(X1-Pad4)") (class "Default")
      (node (ref "X1") (pin "4") (pinfunction "4_4") (pintype "input"))
    )
  )
)
